# RMII_Ethernet.net
KiCad netlist of a schematic drawn in Altium Designer
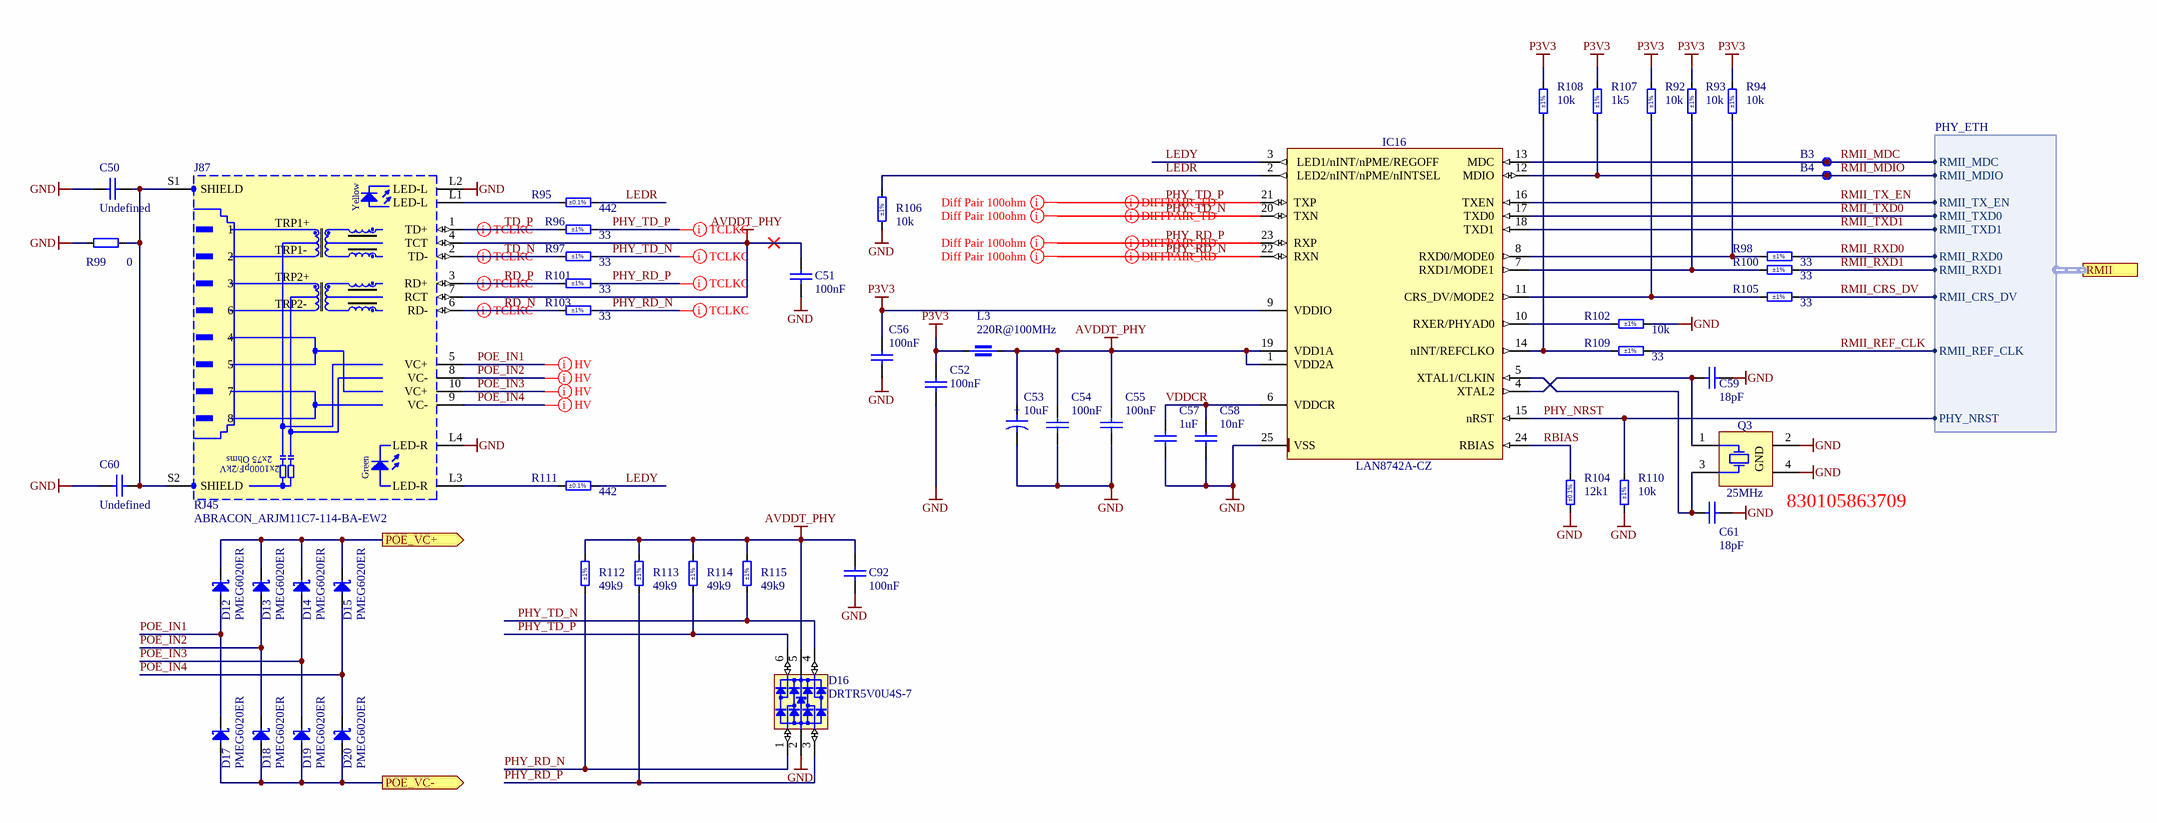
[diagram p0: RMII_Ethernet.SchDoc]

(export (version "E")
  (design (tool "Eeschema 10.0.6"))
  (components
    (comp (ref "B3")
      (value "SMD Pad")
      (footprint "C100")
      (description "Pad")
      (fields (field (name "PART NUMBER") "SMD_PAD_D1MM") (field (name "AUTHOR") "CERN DEM JLC"))
      (libsource (lib "Eletro-mechanical") (part "Single SMD Pad (Round)"))
    )
    (comp (ref "B4")
      (value "SMD Pad")
      (footprint "C100")
      (description "Pad")
      (fields (field (name "PART NUMBER") "SMD_PAD_D1MM") (field (name "AUTHOR") "CERN DEM JLC"))
      (libsource (lib "Eletro-mechanical") (part "Single SMD Pad (Round)"))
    )
    (comp (ref "C50")
      (value "Undefined")
      (footprint "CAPC2012X135N")
      (description "Non-polarised capacitor")
      (fields (field (name "PART NUMBER") "CC0805_NO-VALUE") (field (name "AUTHOR") "CERN DEM JLC"))
      (libsource (lib "Capacitors") (part "Capacitor - non polarized"))
    )
    (comp (ref "C51")
      (value "100nF")
      (footprint "CAPC1608X87N")
      (description "Non-polarised capacitor")
      (fields
        (field (name "PART NUMBER") "CC0603_100NF_50V_10%_X7R")
        (field (name "VOLTAGE") "50V")
        (field (name "AUTHOR") "CERN DEM JLC")
      )
      (libsource (lib "Capacitors") (part "Capacitor - non polarized"))
    )
    (comp (ref "C52")
      (value "100nF")
      (footprint "CAPC1608X87N")
      (description "Non-polarised capacitor")
      (fields
        (field (name "PART NUMBER") "CC0603_100NF_50V_10%_X7R")
        (field (name "VOLTAGE") "50V")
        (field (name "AUTHOR") "CERN DEM JLC")
      )
      (libsource (lib "Capacitors") (part "Capacitor - non polarized"))
    )
    (comp (ref "C53")
      (value "10uF")
      (footprint "CAPMP3216X180N")
      (description "Polarised capacitor")
      (fields
        (field (name "PART NUMBER") "CTE3216-18_10UF_16V_20%_AVX_TCJ")
        (field (name "VOLTAGE") "16V")
        (field (name "AUTHOR") "CERN DEM JLC")
      )
      (libsource (lib "Capacitors") (part "Capacitor - polarized"))
    )
    (comp (ref "C54")
      (value "100nF")
      (footprint "CAPC1608X87N")
      (description "Non-polarised capacitor")
      (fields
        (field (name "PART NUMBER") "CC0603_100NF_50V_10%_X7R")
        (field (name "VOLTAGE") "50V")
        (field (name "AUTHOR") "CERN DEM JLC")
      )
      (libsource (lib "Capacitors") (part "Capacitor - non polarized"))
    )
    (comp (ref "C55")
      (value "100nF")
      (footprint "CAPC1608X87N")
      (description "Non-polarised capacitor")
      (fields
        (field (name "PART NUMBER") "CC0603_100NF_50V_10%_X7R")
        (field (name "VOLTAGE") "50V")
        (field (name "AUTHOR") "CERN DEM JLC")
      )
      (libsource (lib "Capacitors") (part "Capacitor - non polarized"))
    )
    (comp (ref "C56")
      (value "100nF")
      (footprint "CAPC1608X87N")
      (description "Non-polarised capacitor")
      (fields
        (field (name "PART NUMBER") "CC0603_100NF_50V_10%_X7R")
        (field (name "VOLTAGE") "50V")
        (field (name "AUTHOR") "CERN DEM JLC")
      )
      (libsource (lib "Capacitors") (part "Capacitor - non polarized"))
    )
    (comp (ref "C57")
      (value "1uF")
      (footprint "CAPC1608X87N")
      (description "Non-polarised capacitor")
      (fields
        (field (name "PART NUMBER") "CC0603_1UF_16V_10%_X7R")
        (field (name "VOLTAGE") "16V")
        (field (name "AUTHOR") "CERN DEM JLC")
      )
      (libsource (lib "Capacitors") (part "Capacitor - non polarized"))
    )
    (comp (ref "C58")
      (value "10nF")
      (footprint "CAPC1608X87N")
      (description "Non-polarised capacitor")
      (fields
        (field (name "PART NUMBER") "CC0603_10NF_50V_10%_X7R")
        (field (name "VOLTAGE") "50V")
        (field (name "AUTHOR") "CERN DEM JLC")
      )
      (libsource (lib "Capacitors") (part "Capacitor - non polarized"))
    )
    (comp (ref "C59")
      (value "18pF")
      (footprint "CAPC1608X87N")
      (description "Non-polarised capacitor")
      (fields
        (field (name "PART NUMBER") "CC0603_18PF_50V_5%_NP0")
        (field (name "VOLTAGE") "50V")
        (field (name "AUTHOR") "CERN DEM JLC")
      )
      (libsource (lib "Capacitors") (part "Capacitor - non polarized"))
    )
    (comp (ref "C60")
      (value "Undefined")
      (footprint "CAPC2012X135N")
      (description "Non-polarised capacitor")
      (fields (field (name "PART NUMBER") "CC0805_NO-VALUE") (field (name "AUTHOR") "CERN DEM JLC"))
      (libsource (lib "Capacitors") (part "Capacitor - non polarized"))
    )
    (comp (ref "C61")
      (value "18pF")
      (footprint "CAPC1608X87N")
      (description "Non-polarised capacitor")
      (fields
        (field (name "PART NUMBER") "CC0603_18PF_50V_5%_NP0")
        (field (name "VOLTAGE") "50V")
        (field (name "AUTHOR") "CERN DEM JLC")
      )
      (libsource (lib "Capacitors") (part "Capacitor - non polarized"))
    )
    (comp (ref "C92")
      (value "100nF")
      (footprint "CAPC1608X87N")
      (description "Non-polarised capacitor")
      (fields
        (field (name "PART NUMBER") "CC0603_100NF_50V_10%_X7R")
        (field (name "VOLTAGE") "50V")
        (field (name "AUTHOR") "CERN DEM JLC")
      )
      (libsource (lib "Capacitors") (part "Capacitor - non polarized"))
    )
    (comp (ref "D12")
      (value "PMEG6020ER")
      (footprint "SODFL3517X110N")
      (description "Schottky Diode")
      (fields
        (field (name "VOLTAGE") "60V")
        (field (name "POWER") "2A")
        (field (name "AUTHOR") "CERN DEM JMW")
      )
      (libsource (lib "ICs And Semiconductors") (part "Diode Schottky"))
    )
    (comp (ref "D13")
      (value "PMEG6020ER")
      (footprint "SODFL3517X110N")
      (description "Schottky Diode")
      (fields
        (field (name "VOLTAGE") "60V")
        (field (name "POWER") "2A")
        (field (name "AUTHOR") "CERN DEM JMW")
      )
      (libsource (lib "ICs And Semiconductors") (part "Diode Schottky"))
    )
    (comp (ref "D14")
      (value "PMEG6020ER")
      (footprint "SODFL3517X110N")
      (description "Schottky Diode")
      (fields
        (field (name "VOLTAGE") "60V")
        (field (name "POWER") "2A")
        (field (name "AUTHOR") "CERN DEM JMW")
      )
      (libsource (lib "ICs And Semiconductors") (part "Diode Schottky"))
    )
    (comp (ref "D15")
      (value "PMEG6020ER")
      (footprint "SODFL3517X110N")
      (description "Schottky Diode")
      (fields
        (field (name "VOLTAGE") "60V")
        (field (name "POWER") "2A")
        (field (name "AUTHOR") "CERN DEM JMW")
      )
      (libsource (lib "ICs And Semiconductors") (part "Diode Schottky"))
    )
    (comp (ref "D16")
      (value "DRTR5V0U4S-7")
      (footprint "SOT65P210X110-6N")
      (description "Integrated Quad Ultra-Low Capacitance ESD Protection")
      (fields (field (name "MANUFACTURER") "DIODES") (field (name "AUTHOR") "GK"))
      (libsource (lib "Diodes") (part "D_TVS_DRTR5V0U4S-7"))
    )
    (comp (ref "D17")
      (value "PMEG6020ER")
      (footprint "SODFL3517X110N")
      (description "Schottky Diode")
      (fields
        (field (name "VOLTAGE") "60V")
        (field (name "POWER") "2A")
        (field (name "AUTHOR") "CERN DEM JMW")
      )
      (libsource (lib "ICs And Semiconductors") (part "Diode Schottky"))
    )
    (comp (ref "D18")
      (value "PMEG6020ER")
      (footprint "SODFL3517X110N")
      (description "Schottky Diode")
      (fields
        (field (name "VOLTAGE") "60V")
        (field (name "POWER") "2A")
        (field (name "AUTHOR") "CERN DEM JMW")
      )
      (libsource (lib "ICs And Semiconductors") (part "Diode Schottky"))
    )
    (comp (ref "D19")
      (value "PMEG6020ER")
      (footprint "SODFL3517X110N")
      (description "Schottky Diode")
      (fields
        (field (name "VOLTAGE") "60V")
        (field (name "POWER") "2A")
        (field (name "AUTHOR") "CERN DEM JMW")
      )
      (libsource (lib "ICs And Semiconductors") (part "Diode Schottky"))
    )
    (comp (ref "D20")
      (value "PMEG6020ER")
      (footprint "SODFL3517X110N")
      (description "Schottky Diode")
      (fields
        (field (name "VOLTAGE") "60V")
        (field (name "POWER") "2A")
        (field (name "AUTHOR") "CERN DEM JMW")
      )
      (libsource (lib "ICs And Semiconductors") (part "Diode Schottky"))
    )
    (comp (ref "IC16")
      (value "LAN8742A-CZ")
      (footprint "MICROCHIP_C04-143B")
      (description "10/100 Base-T/TX Ethernet Transceiver with Cable Diagnostics")
      (fields (field (name "MANUFACTURER") "MICROCHIP TECHNOLOGY") (field (name "AUTHOR") "CERN DEM HF"))
      (libsource (lib "ICs And Semiconductors") (part "LAN8742A-CZ"))
    )
    (comp (ref "J87")
      (value "RJ45")
      (footprint "ABRACON_ARJM11C7-114-BA-EW2")
      (description "MagJack 10/100BaseT, PoE+, 1X1, OG/Y, -40 to 85*C, Tab Up, RoHS")
      (fields
        (field (name "PART NUMBER") "5-2337992-3")
        (field (name "MANUFACTURER") "TE")
        (field (name "AUTHOR") "GK")
      )
      (libsource (lib "LIBRARY_SCH") (part "CON_ETH_POE_ARJM11C7"))
    )
    (comp (ref "L3")
      (value "220R@100MHz")
      (footprint "INDC1608X95N")
      (fields
        (field (name "PART NUMBER") "IND0603_MURATA_BLM18SG221TN1")
        (field (name "POWER") "2.5A")
        (field (name "TOLERANCE") "±25%")
        (field (name "AUTHOR") "CERN DEM MR")
      )
      (libsource (lib "Inductors & Transformers") (part "Ferrite Bead"))
    )
    (comp (ref "Q3")
      (value "25MHz")
      (footprint "XTAL_TXC_8Y")
      (description "Crystal 4 pins 1=XTAL Control 2=GND3=XTAL 4=GND")
      (fields
        (field (name "PART NUMBER") "XTAL_25MHZ_TXC_8Y-25.000MAAJ-T")
        (field (name "MANUFACTURER") "TXC CORPORATION")
        (field (name "AUTHOR") "CERN DEM JLC")
      )
      (libsource (lib "ICs And Semiconductors") (part "Quartz Crystal 1X 2GND 3X 4GND"))
    )
    (comp (ref "R92")
      (value "10k")
      (footprint "RESC1608X55N")
      (description "Resistor - 1%")
      (fields
        (field (name "TOLERANCE") "±1%")
        (field (name "PART NUMBER") "R0603_10K_1%_0.1W_100PPM")
        (field (name "POWER") "0.1W")
        (field (name "AUTHOR") "CERN DEM JLC")
      )
      (libsource (lib "Resistors") (part "Resistor - 1%"))
    )
    (comp (ref "R93")
      (value "10k")
      (footprint "RESC1608X55N")
      (description "Resistor - 1%")
      (fields
        (field (name "TOLERANCE") "±1%")
        (field (name "PART NUMBER") "R0603_10K_1%_0.1W_100PPM")
        (field (name "POWER") "0.1W")
        (field (name "AUTHOR") "CERN DEM JLC")
      )
      (libsource (lib "Resistors") (part "Resistor - 1%"))
    )
    (comp (ref "R94")
      (value "10k")
      (footprint "RESC1608X55N")
      (description "Resistor - 1%")
      (fields
        (field (name "TOLERANCE") "±1%")
        (field (name "PART NUMBER") "R0603_10K_1%_0.1W_100PPM")
        (field (name "POWER") "0.1W")
        (field (name "AUTHOR") "CERN DEM JLC")
      )
      (libsource (lib "Resistors") (part "Resistor - 1%"))
    )
    (comp (ref "R95")
      (value "442")
      (footprint "RESC1608X55N")
      (description "Resistor - 0.1%")
      (fields
        (field (name "TOLERANCE") "±0.1%")
        (field (name "PART NUMBER") "R0603_442R_0.1%_0.063W_10PPM")
        (field (name "POWER") "0.063W")
        (field (name "AUTHOR") "CERN DEM JLC")
      )
      (libsource (lib "Resistors") (part "Resistor - 0.1%"))
    )
    (comp (ref "R96")
      (value "33")
      (footprint "RESC1608X55N")
      (description "Resistor - 1%")
      (fields
        (field (name "TOLERANCE") "±1%")
        (field (name "PART NUMBER") "R0603_33R_1%_0.1W_100PPM")
        (field (name "POWER") "0.1W")
        (field (name "AUTHOR") "CERN DEM JLC")
      )
      (libsource (lib "Resistors") (part "Resistor - 1%"))
    )
    (comp (ref "R97")
      (value "33")
      (footprint "RESC1608X55N")
      (description "Resistor - 1%")
      (fields
        (field (name "TOLERANCE") "±1%")
        (field (name "PART NUMBER") "R0603_33R_1%_0.1W_100PPM")
        (field (name "POWER") "0.1W")
        (field (name "AUTHOR") "CERN DEM JLC")
      )
      (libsource (lib "Resistors") (part "Resistor - 1%"))
    )
    (comp (ref "R98")
      (value "33")
      (footprint "RESC1608X55N")
      (description "Resistor - 1%")
      (fields
        (field (name "TOLERANCE") "±1%")
        (field (name "PART NUMBER") "R0603_33R_1%_0.1W_100PPM")
        (field (name "POWER") "0.1W")
        (field (name "AUTHOR") "CERN DEM JLC")
      )
      (libsource (lib "Resistors") (part "Resistor - 1%"))
    )
    (comp (ref "R99")
      (value "0")
      (footprint "RESC1608X55N")
      (description "Resistor")
      (fields
        (field (name "PART NUMBER") "R0603_0R_JUMPER")
        (field (name "MANUFACTURER") "GENERIC")
        (field (name "AUTHOR") "CERN DEM JLC")
      )
      (libsource (lib "Resistors") (part "Resistor"))
    )
    (comp (ref "R100")
      (value "33")
      (footprint "RESC1608X55N")
      (description "Resistor - 1%")
      (fields
        (field (name "TOLERANCE") "±1%")
        (field (name "PART NUMBER") "R0603_33R_1%_0.1W_100PPM")
        (field (name "POWER") "0.1W")
        (field (name "AUTHOR") "CERN DEM JLC")
      )
      (libsource (lib "Resistors") (part "Resistor - 1%"))
    )
    (comp (ref "R101")
      (value "33")
      (footprint "RESC1608X55N")
      (description "Resistor - 1%")
      (fields
        (field (name "TOLERANCE") "±1%")
        (field (name "PART NUMBER") "R0603_33R_1%_0.1W_100PPM")
        (field (name "POWER") "0.1W")
        (field (name "AUTHOR") "CERN DEM JLC")
      )
      (libsource (lib "Resistors") (part "Resistor - 1%"))
    )
    (comp (ref "R102")
      (value "10k")
      (footprint "RESC1608X55N")
      (description "Resistor - 1%")
      (fields
        (field (name "TOLERANCE") "±1%")
        (field (name "PART NUMBER") "R0603_10K_1%_0.1W_100PPM")
        (field (name "POWER") "0.1W")
        (field (name "AUTHOR") "CERN DEM JLC")
      )
      (libsource (lib "Resistors") (part "Resistor - 1%"))
    )
    (comp (ref "R103")
      (value "33")
      (footprint "RESC1608X55N")
      (description "Resistor - 1%")
      (fields
        (field (name "TOLERANCE") "±1%")
        (field (name "PART NUMBER") "R0603_33R_1%_0.1W_100PPM")
        (field (name "POWER") "0.1W")
        (field (name "AUTHOR") "CERN DEM JLC")
      )
      (libsource (lib "Resistors") (part "Resistor - 1%"))
    )
    (comp (ref "R104")
      (value "12k1")
      (footprint "RESC1608X55N")
      (description "Resistor - 0.1%")
      (fields
        (field (name "TOLERANCE") "±0.1%")
        (field (name "PART NUMBER") "R0603_12K1_0.1%_0.063W_10PPM")
        (field (name "POWER") "0.063W")
        (field (name "AUTHOR") "CERN DEM JLC")
      )
      (libsource (lib "Resistors") (part "Resistor - 0.1%"))
    )
    (comp (ref "R105")
      (value "33")
      (footprint "RESC1608X55N")
      (description "Resistor - 1%")
      (fields
        (field (name "TOLERANCE") "±1%")
        (field (name "PART NUMBER") "R0603_33R_1%_0.1W_100PPM")
        (field (name "POWER") "0.1W")
        (field (name "AUTHOR") "CERN DEM JLC")
      )
      (libsource (lib "Resistors") (part "Resistor - 1%"))
    )
    (comp (ref "R106")
      (value "10k")
      (footprint "RESC1608X55N")
      (description "Resistor - 1%")
      (fields
        (field (name "TOLERANCE") "±1%")
        (field (name "PART NUMBER") "R0603_10K_1%_0.1W_100PPM")
        (field (name "POWER") "0.1W")
        (field (name "AUTHOR") "CERN DEM JLC")
      )
      (libsource (lib "Resistors") (part "Resistor - 1%"))
    )
    (comp (ref "R107")
      (value "1k5")
      (footprint "RESC1608X55N")
      (description "Resistor - 1%")
      (fields
        (field (name "TOLERANCE") "±1%")
        (field (name "PART NUMBER") "R0603_1K5_1%_0.1W_100PPM")
        (field (name "POWER") "0.1W")
        (field (name "AUTHOR") "CERN DEM JLC")
      )
      (libsource (lib "Resistors") (part "Resistor - 1%"))
    )
    (comp (ref "R108")
      (value "10k")
      (footprint "RESC1608X55N")
      (description "Resistor - 1%")
      (fields
        (field (name "TOLERANCE") "±1%")
        (field (name "PART NUMBER") "R0603_10K_1%_0.1W_100PPM")
        (field (name "POWER") "0.1W")
        (field (name "AUTHOR") "CERN DEM JLC")
      )
      (libsource (lib "Resistors") (part "Resistor - 1%"))
    )
    (comp (ref "R109")
      (value "33")
      (footprint "RESC1608X55N")
      (description "Resistor - 1%")
      (fields
        (field (name "TOLERANCE") "±1%")
        (field (name "PART NUMBER") "R0603_33R_1%_0.1W_100PPM")
        (field (name "POWER") "0.1W")
        (field (name "AUTHOR") "CERN DEM JLC")
      )
      (libsource (lib "Resistors") (part "Resistor - 1%"))
    )
    (comp (ref "R110")
      (value "10k")
      (footprint "RESC1608X55N")
      (description "Resistor - 1%")
      (fields
        (field (name "TOLERANCE") "±1%")
        (field (name "PART NUMBER") "R0603_10K_1%_0.1W_100PPM")
        (field (name "POWER") "0.1W")
        (field (name "AUTHOR") "CERN DEM JLC")
      )
      (libsource (lib "Resistors") (part "Resistor - 1%"))
    )
    (comp (ref "R111")
      (value "442")
      (footprint "RESC1608X55N")
      (description "Resistor - 0.1%")
      (fields
        (field (name "TOLERANCE") "±0.1%")
        (field (name "PART NUMBER") "R0603_442R_0.1%_0.063W_10PPM")
        (field (name "POWER") "0.063W")
        (field (name "AUTHOR") "CERN DEM JLC")
      )
      (libsource (lib "Resistors") (part "Resistor - 0.1%"))
    )
    (comp (ref "R112")
      (value "49k9")
      (footprint "RESC1608X55N")
      (description "Resistor - 1%")
      (fields
        (field (name "TOLERANCE") "±1%")
        (field (name "PART NUMBER") "R0603_49K9_1%_0.1W_100PPM")
        (field (name "POWER") "0.1W")
        (field (name "AUTHOR") "CERN DEM JLC")
      )
      (libsource (lib "Resistors") (part "Resistor - 1%"))
    )
    (comp (ref "R113")
      (value "49k9")
      (footprint "RESC1608X55N")
      (description "Resistor - 1%")
      (fields
        (field (name "TOLERANCE") "±1%")
        (field (name "PART NUMBER") "R0603_49K9_1%_0.1W_100PPM")
        (field (name "POWER") "0.1W")
        (field (name "AUTHOR") "CERN DEM JLC")
      )
      (libsource (lib "Resistors") (part "Resistor - 1%"))
    )
    (comp (ref "R114")
      (value "49k9")
      (footprint "RESC1608X55N")
      (description "Resistor - 1%")
      (fields
        (field (name "TOLERANCE") "±1%")
        (field (name "PART NUMBER") "R0603_49K9_1%_0.1W_100PPM")
        (field (name "POWER") "0.1W")
        (field (name "AUTHOR") "CERN DEM JLC")
      )
      (libsource (lib "Resistors") (part "Resistor - 1%"))
    )
    (comp (ref "R115")
      (value "49k9")
      (footprint "RESC1608X55N")
      (description "Resistor - 1%")
      (fields
        (field (name "TOLERANCE") "±1%")
        (field (name "PART NUMBER") "R0603_49K9_1%_0.1W_100PPM")
        (field (name "POWER") "0.1W")
        (field (name "AUTHOR") "CERN DEM JLC")
      )
      (libsource (lib "Resistors") (part "Resistor - 1%"))
    )
  )
  (nets
    (net (code "2") (name "/LEDR") (class "Default")
      (node (ref "IC16") (pin "2") (pinfunction "_LED2/nINT/nPME/nINTSEL_2") (pintype "output"))
      (node (ref "R106") (pin "2") (pinfunction "2_2") (pintype "passive"))
      (node (ref "R95") (pin "2") (pinfunction "2_2") (pintype "passive"))
    )
    (net (code "3") (name "/LEDY") (class "Default")
      (node (ref "IC16") (pin "3") (pinfunction "_LED1/nINT/nPME/REGOFF_3") (pintype "output"))
      (node (ref "R111") (pin "2") (pinfunction "2_2") (pintype "passive"))
    )
    (net (code "4") (name "/PHY_NRST") (class "Default")
      (node (ref "IC16") (pin "15") (pinfunction "nRST_15") (pintype "input"))
      (node (ref "R110") (pin "2") (pinfunction "2_2") (pintype "passive"))
    )
    (net (code "5") (name "/PHY_RD_N") (class "Default")
      (node (ref "D16") (pin "1") (pinfunction "I/O1_1") (pintype "bidirectional"))
      (node (ref "IC16") (pin "22") (pinfunction "RXN_22") (pintype "bidirectional"))
      (node (ref "R103") (pin "1") (pinfunction "1_1") (pintype "passive"))
      (node (ref "R112") (pin "1") (pinfunction "1_1") (pintype "passive"))
    )
    (net (code "6") (name "/PHY_RD_P") (class "Default")
      (node (ref "D16") (pin "3") (pinfunction "I/O2_3") (pintype "bidirectional"))
      (node (ref "IC16") (pin "23") (pinfunction "RXP_23") (pintype "bidirectional"))
      (node (ref "R101") (pin "1") (pinfunction "1_1") (pintype "passive"))
      (node (ref "R113") (pin "1") (pinfunction "1_1") (pintype "passive"))
    )
    (net (code "7") (name "/PHY_TD_N") (class "Default")
      (node (ref "D16") (pin "4") (pinfunction "I/O3_4") (pintype "bidirectional"))
      (node (ref "IC16") (pin "20") (pinfunction "TXN_20") (pintype "bidirectional"))
      (node (ref "R115") (pin "1") (pinfunction "1_1") (pintype "passive"))
      (node (ref "R97") (pin "1") (pinfunction "1_1") (pintype "passive"))
    )
    (net (code "8") (name "/PHY_TD_P") (class "Default")
      (node (ref "D16") (pin "6") (pinfunction "I/O4_6") (pintype "bidirectional"))
      (node (ref "IC16") (pin "21") (pinfunction "TXP_21") (pintype "bidirectional"))
      (node (ref "R114") (pin "1") (pinfunction "1_1") (pintype "passive"))
      (node (ref "R96") (pin "1") (pinfunction "1_1") (pintype "passive"))
    )
    (net (code "9") (name "/POE_IN1") (class "Default")
      (node (ref "D12") (pin "2") (pinfunction "A_2") (pintype "passive"))
      (node (ref "D17") (pin "1") (pinfunction "C_1") (pintype "passive"))
      (node (ref "J87") (pin "5") (pinfunction "VC+_5") (pintype "passive"))
    )
    (net (code "10") (name "/POE_IN2") (class "Default")
      (node (ref "D13") (pin "2") (pinfunction "A_2") (pintype "passive"))
      (node (ref "D18") (pin "1") (pinfunction "C_1") (pintype "passive"))
      (node (ref "J87") (pin "8") (pinfunction "VC-_8") (pintype "passive"))
    )
    (net (code "11") (name "/POE_IN3") (class "Default")
      (node (ref "D14") (pin "2") (pinfunction "A_2") (pintype "passive"))
      (node (ref "D19") (pin "1") (pinfunction "C_1") (pintype "passive"))
      (node (ref "J87") (pin "10") (pinfunction "VC+_10") (pintype "passive"))
    )
    (net (code "12") (name "/POE_IN4") (class "Default")
      (node (ref "D15") (pin "2") (pinfunction "A_2") (pintype "passive"))
      (node (ref "D20") (pin "1") (pinfunction "C_1") (pintype "passive"))
      (node (ref "J87") (pin "9") (pinfunction "VC-_9") (pintype "passive"))
    )
    (net (code "13") (name "/POE_VC+") (class "Default")
      (node (ref "D12") (pin "1") (pinfunction "C_1") (pintype "passive"))
      (node (ref "D13") (pin "1") (pinfunction "C_1") (pintype "passive"))
      (node (ref "D14") (pin "1") (pinfunction "C_1") (pintype "passive"))
      (node (ref "D15") (pin "1") (pinfunction "C_1") (pintype "passive"))
    )
    (net (code "14") (name "/POE_VC-") (class "Default")
      (node (ref "D17") (pin "2") (pinfunction "A_2") (pintype "passive"))
      (node (ref "D18") (pin "2") (pinfunction "A_2") (pintype "passive"))
      (node (ref "D19") (pin "2") (pinfunction "A_2") (pintype "passive"))
      (node (ref "D20") (pin "2") (pinfunction "A_2") (pintype "passive"))
    )
    (net (code "15") (name "/RBIAS") (class "Default")
      (node (ref "IC16") (pin "24") (pinfunction "RBIAS_24") (pintype "input"))
      (node (ref "R104") (pin "1") (pinfunction "1_1") (pintype "passive"))
    )
    (net (code "16") (name "/RD_N") (class "Default")
      (node (ref "J87") (pin "6") (pinfunction "RD-_6") (pintype "bidirectional"))
      (node (ref "R103") (pin "2") (pinfunction "2_2") (pintype "passive"))
    )
    (net (code "17") (name "/RD_P") (class "Default")
      (node (ref "J87") (pin "3") (pinfunction "RD+_3") (pintype "bidirectional"))
      (node (ref "R101") (pin "2") (pinfunction "2_2") (pintype "passive"))
    )
    (net (code "18") (name "/RMII_CRS_DV") (class "Default")
      (node (ref "R105") (pin "1") (pinfunction "1_1") (pintype "passive"))
    )
    (net (code "19") (name "/RMII_MDC") (class "Default")
      (node (ref "B3") (pin "1") (pinfunction "1_1") (pintype "bidirectional"))
      (node (ref "IC16") (pin "13") (pinfunction "MDC_13") (pintype "input"))
    )
    (net (code "20") (name "/RMII_MDIO") (class "Default")
      (node (ref "B4") (pin "1") (pinfunction "1_1") (pintype "bidirectional"))
      (node (ref "IC16") (pin "12") (pinfunction "MDIO_12") (pintype "bidirectional"))
      (node (ref "R107") (pin "2") (pinfunction "2_2") (pintype "passive"))
    )
    (net (code "21") (name "/RMII_REF_CLK") (class "Default")
      (node (ref "R109") (pin "1") (pinfunction "1_1") (pintype "passive"))
    )
    (net (code "22") (name "/RMII_RXD0") (class "Default")
      (node (ref "R98") (pin "1") (pinfunction "1_1") (pintype "passive"))
    )
    (net (code "23") (name "/RMII_RXD1") (class "Default")
      (node (ref "R100") (pin "1") (pinfunction "1_1") (pintype "passive"))
    )
    (net (code "24") (name "/RMII_TXD0") (class "Default")
      (node (ref "IC16") (pin "17") (pinfunction "TXD0_17") (pintype "input"))
    )
    (net (code "25") (name "/RMII_TXD1") (class "Default")
      (node (ref "IC16") (pin "18") (pinfunction "TXD1_18") (pintype "input"))
    )
    (net (code "26") (name "/RMII_TX_EN") (class "Default")
      (node (ref "IC16") (pin "16") (pinfunction "TXEN_16") (pintype "input"))
    )
    (net (code "27") (name "/TD_N") (class "Default")
      (node (ref "J87") (pin "2") (pinfunction "TD-_2") (pintype "bidirectional"))
      (node (ref "R97") (pin "2") (pinfunction "2_2") (pintype "passive"))
    )
    (net (code "28") (name "/TD_P") (class "Default")
      (node (ref "J87") (pin "1") (pinfunction "TD+_1") (pintype "bidirectional"))
      (node (ref "R96") (pin "2") (pinfunction "2_2") (pintype "passive"))
    )
    (net (code "29") (name "/VDDCR") (class "Default")
      (node (ref "C57") (pin "2") (pinfunction "2_2") (pintype "passive"))
      (node (ref "C58") (pin "2") (pinfunction "2_2") (pintype "passive"))
      (node (ref "IC16") (pin "6") (pinfunction "VDDCR_6") (pintype "power_in"))
    )
    (net (code "31") (name "AVDDT_PHY") (class "Default")
      (node (ref "C51") (pin "2") (pinfunction "2_2") (pintype "passive"))
      (node (ref "C53") (pin "1") (pinfunction "1_1") (pintype "passive"))
      (node (ref "C54") (pin "2") (pinfunction "2_2") (pintype "passive"))
      (node (ref "C55") (pin "2") (pinfunction "2_2") (pintype "passive"))
      (node (ref "C92") (pin "2") (pinfunction "2_2") (pintype "passive"))
      (node (ref "D16") (pin "5") (pinfunction "VBUS_5") (pintype "power_in"))
      (node (ref "IC16") (pin "1") (pinfunction "VDD2A_1") (pintype "power_in"))
      (node (ref "IC16") (pin "19") (pinfunction "VDD1A_19") (pintype "power_in"))
      (node (ref "J87") (pin "4") (pinfunction "TCT_4") (pintype "bidirectional"))
      (node (ref "J87") (pin "7") (pinfunction "RCT_7") (pintype "bidirectional"))
      (node (ref "L3") (pin "2") (pinfunction "2_2") (pintype "passive"))
      (node (ref "R112") (pin "2") (pinfunction "2_2") (pintype "passive"))
      (node (ref "R113") (pin "2") (pinfunction "2_2") (pintype "passive"))
      (node (ref "R114") (pin "2") (pinfunction "2_2") (pintype "passive"))
      (node (ref "R115") (pin "2") (pinfunction "2_2") (pintype "passive"))
    )
    (net (code "32") (name "GND") (class "Default")
      (node (ref "C50") (pin "2") (pinfunction "2_2") (pintype "passive"))
      (node (ref "C51") (pin "1") (pinfunction "1_1") (pintype "passive"))
      (node (ref "C52") (pin "1") (pinfunction "1_1") (pintype "passive"))
      (node (ref "C53") (pin "2") (pinfunction "2_2") (pintype "passive"))
      (node (ref "C54") (pin "1") (pinfunction "1_1") (pintype "passive"))
      (node (ref "C55") (pin "1") (pinfunction "1_1") (pintype "passive"))
      (node (ref "C56") (pin "1") (pinfunction "1_1") (pintype "passive"))
      (node (ref "C57") (pin "1") (pinfunction "1_1") (pintype "passive"))
      (node (ref "C58") (pin "1") (pinfunction "1_1") (pintype "passive"))
      (node (ref "C59") (pin "1") (pinfunction "1_1") (pintype "passive"))
      (node (ref "C60") (pin "2") (pinfunction "2_2") (pintype "passive"))
      (node (ref "C61") (pin "1") (pinfunction "1_1") (pintype "passive"))
      (node (ref "C92") (pin "1") (pinfunction "1_1") (pintype "passive"))
      (node (ref "D16") (pin "2") (pinfunction "GND_2") (pintype "power_in"))
      (node (ref "IC16") (pin "25") (pinfunction "VSS_25") (pintype "power_in"))
      (node (ref "J87") (pin "L2") (pinfunction "LED-L_L2") (pintype "passive"))
      (node (ref "J87") (pin "L4") (pinfunction "LED-R_L4") (pintype "passive"))
      (node (ref "Q3") (pin "2") (pinfunction "GND_2") (pintype "power_in"))
      (node (ref "Q3") (pin "4") (pinfunction "GND_4") (pintype "power_in"))
      (node (ref "R102") (pin "1") (pinfunction "1_1") (pintype "passive"))
      (node (ref "R104") (pin "2") (pinfunction "2_2") (pintype "passive"))
      (node (ref "R106") (pin "1") (pinfunction "1_1") (pintype "passive"))
      (node (ref "R110") (pin "1") (pinfunction "1_1") (pintype "passive"))
      (node (ref "R99") (pin "1") (pinfunction "1_1") (pintype "passive"))
    )
    (net (code "33") (name "Net-(C50-Pad1)") (class "Default")
      (node (ref "C50") (pin "1") (pinfunction "1_1") (pintype "passive"))
      (node (ref "C60") (pin "1") (pinfunction "1_1") (pintype "passive"))
      (node (ref "J87") (pin "S1") (pinfunction "SHIELD_S1") (pintype "power_in"))
      (node (ref "J87") (pin "S2") (pinfunction "SHIELD_S2") (pintype "power_in"))
      (node (ref "R99") (pin "2") (pinfunction "2_2") (pintype "passive"))
    )
    (net (code "34") (name "Net-(IC16-CRS_DV{slash}MODE2)") (class "Default")
      (node (ref "IC16") (pin "11") (pinfunction "CRS_DV/MODE2_11") (pintype "output"))
      (node (ref "R105") (pin "2") (pinfunction "2_2") (pintype "passive"))
      (node (ref "R92") (pin "1") (pinfunction "1_1") (pintype "passive"))
    )
    (net (code "35") (name "Net-(IC16-RXD0{slash}MODE0)") (class "Default")
      (node (ref "IC16") (pin "8") (pinfunction "RXD0/MODE0_8") (pintype "output"))
      (node (ref "R94") (pin "1") (pinfunction "1_1") (pintype "passive"))
      (node (ref "R98") (pin "2") (pinfunction "2_2") (pintype "passive"))
    )
    (net (code "36") (name "Net-(IC16-RXD1{slash}MODE1)") (class "Default")
      (node (ref "IC16") (pin "7") (pinfunction "RXD1/MODE1_7") (pintype "output"))
      (node (ref "R100") (pin "2") (pinfunction "2_2") (pintype "passive"))
      (node (ref "R93") (pin "1") (pinfunction "1_1") (pintype "passive"))
    )
    (net (code "37") (name "Net-(IC16-RXER{slash}PHYAD0)") (class "Default")
      (node (ref "IC16") (pin "10") (pinfunction "RXER/PHYAD0_10") (pintype "output"))
      (node (ref "R102") (pin "2") (pinfunction "2_2") (pintype "passive"))
    )
    (net (code "38") (name "Net-(IC16-XTAL1{slash}CLKIN)") (class "Default")
      (node (ref "C61") (pin "2") (pinfunction "2_2") (pintype "passive"))
      (node (ref "IC16") (pin "5") (pinfunction "XTAL1/CLKIN_5") (pintype "input"))
      (node (ref "Q3") (pin "3") (pinfunction "X_3") (pintype "passive"))
    )
    (net (code "39") (name "Net-(IC16-XTAL2)") (class "Default")
      (node (ref "C59") (pin "2") (pinfunction "2_2") (pintype "passive"))
      (node (ref "IC16") (pin "4") (pinfunction "XTAL2_4") (pintype "output"))
      (node (ref "Q3") (pin "1") (pinfunction "X_1") (pintype "passive"))
    )
    (net (code "40") (name "Net-(IC16-nINT{slash}REFCLKO)") (class "Default")
      (node (ref "IC16") (pin "14") (pinfunction "nINT/REFCLKO_14") (pintype "output"))
      (node (ref "R108") (pin "2") (pinfunction "2_2") (pintype "passive"))
      (node (ref "R109") (pin "2") (pinfunction "2_2") (pintype "passive"))
    )
    (net (code "41") (name "Net-(J87-LED-L-PadL1)") (class "Default")
      (node (ref "J87") (pin "L1") (pinfunction "LED-L_L1") (pintype "passive"))
      (node (ref "R95") (pin "1") (pinfunction "1_1") (pintype "passive"))
    )
    (net (code "42") (name "Net-(J87-LED-R-PadL3)") (class "Default")
      (node (ref "J87") (pin "L3") (pinfunction "LED-R_L3") (pintype "passive"))
      (node (ref "R111") (pin "1") (pinfunction "1_1") (pintype "passive"))
    )
    (net (code "43") (name "P3V3") (class "Default")
      (node (ref "C52") (pin "2") (pinfunction "2_2") (pintype "passive"))
      (node (ref "C56") (pin "2") (pinfunction "2_2") (pintype "passive"))
      (node (ref "IC16") (pin "9") (pinfunction "VDDIO_9") (pintype "power_in"))
      (node (ref "L3") (pin "1") (pinfunction "1_1") (pintype "passive"))
      (node (ref "R107") (pin "1") (pinfunction "1_1") (pintype "passive"))
      (node (ref "R108") (pin "1") (pinfunction "1_1") (pintype "passive"))
      (node (ref "R92") (pin "2") (pinfunction "2_2") (pintype "passive"))
      (node (ref "R93") (pin "2") (pinfunction "2_2") (pintype "passive"))
      (node (ref "R94") (pin "2") (pinfunction "2_2") (pintype "passive"))
    )
  )
)
